# IPMI.net
KiCad netlist of a schematic drawn in Altium Designer
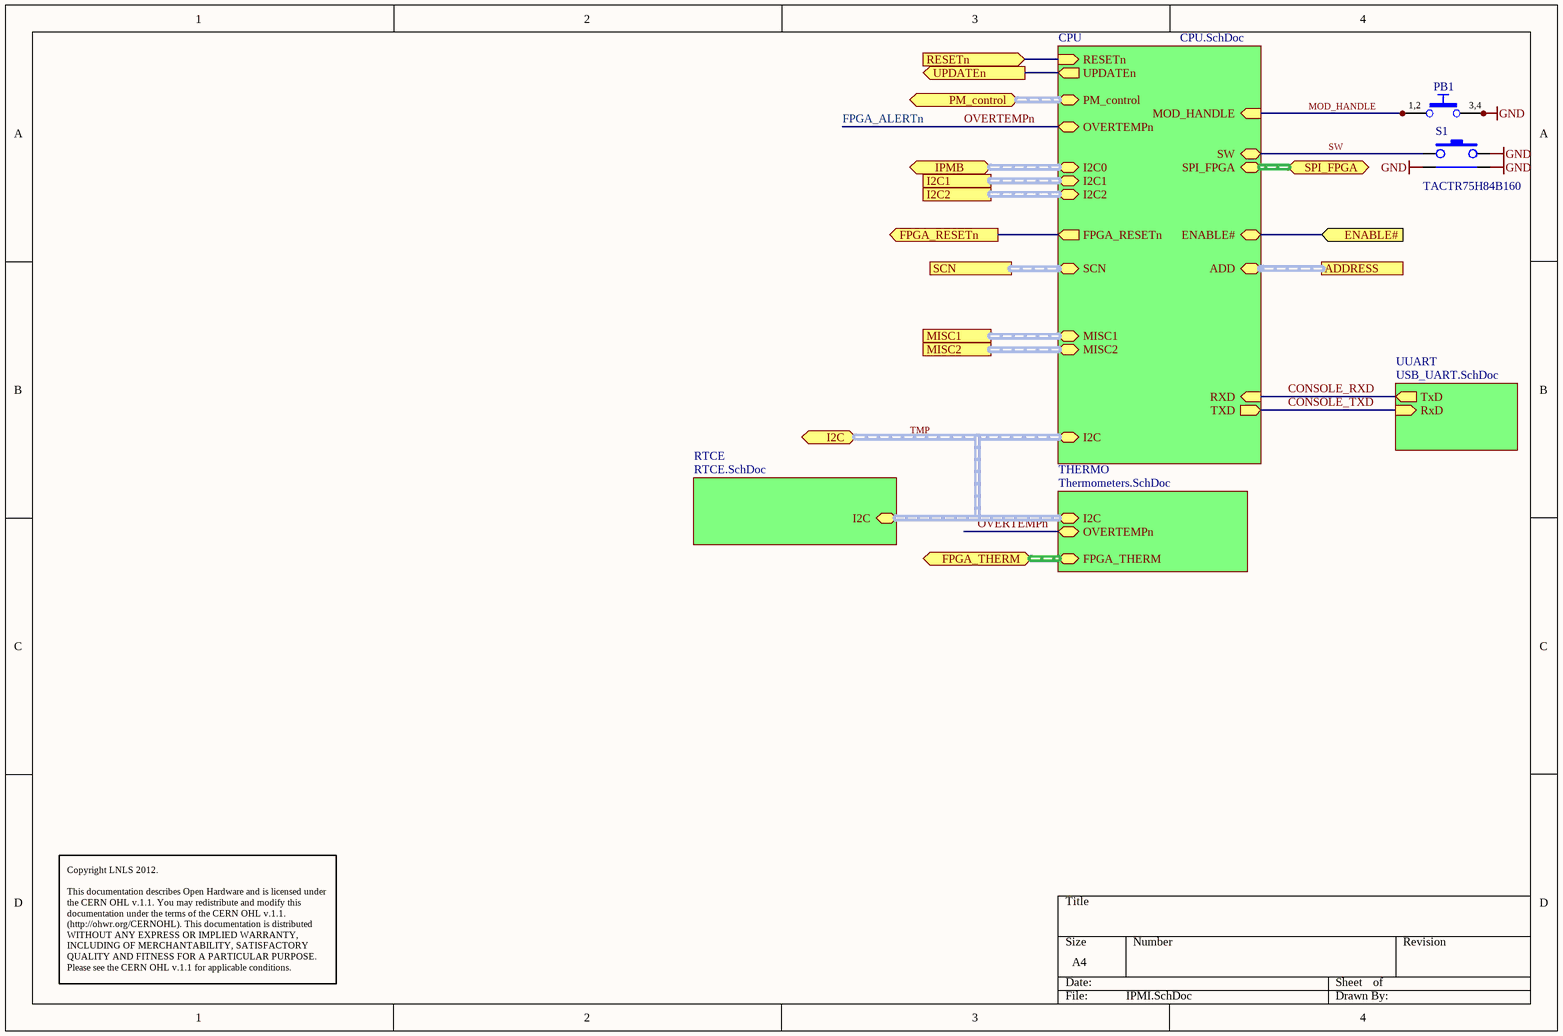
[diagram p0: IPMI.SchDoc]

(export (version "E")
  (design (tool "Eeschema 10.0.6"))
  (components
    (comp (ref "PB1")
      (value "Push Button")
      (footprint "SW_C&K_HDT0001")
      (description "Push-Button Switch SPDT")
      (fields
        (field (name "PART NUMBER") "SW_C&K_HDT0001")
        (field (name "MANUFACTURER") "C&K")
        (field (name "AUTHOR") "CERN DEM JLC")
      )
      (libsource (lib "Eletro-mechanical") (part "PB SPST 12NO-34NO"))
    )
    (comp (ref "S1")
      (value "TACTR75H84B160")
      (footprint "PB_ALPS_SKHHLQA010")
      (description "Push button")
      (libsource (lib "LIBRARY_SCH") (part "SW-PB_RA_5.8mm"))
    )
  )
  (nets
    (net (code "24") (name "/MOD_HANDLE") (class "Default")
      (node (ref "PB1") (pin "1") (pinfunction "1_1") (pintype "passive"))
      (node (ref "PB1") (pin "2") (pinfunction "2_2") (pintype "passive"))
    )
    (net (code "29") (name "/SW") (class "Default")
      (node (ref "S1") (pin "1") (pinfunction "1_1") (pintype "passive"))
    )
    (net (code "32") (name "GND") (class "Default")
      (node (ref "PB1") (pin "3") (pinfunction "3_3") (pintype "passive"))
      (node (ref "PB1") (pin "4") (pinfunction "4_4") (pintype "passive"))
      (node (ref "S1") (pin "2") (pinfunction "2_2") (pintype "passive"))
      (node (ref "S1") (pin "3") (pinfunction "3_3") (pintype "passive"))
      (node (ref "S1") (pin "4") (pinfunction "4_4") (pintype "passive"))
    )
  )
)
